# sensors.net
KiCad netlist of a schematic drawn in EAGLE
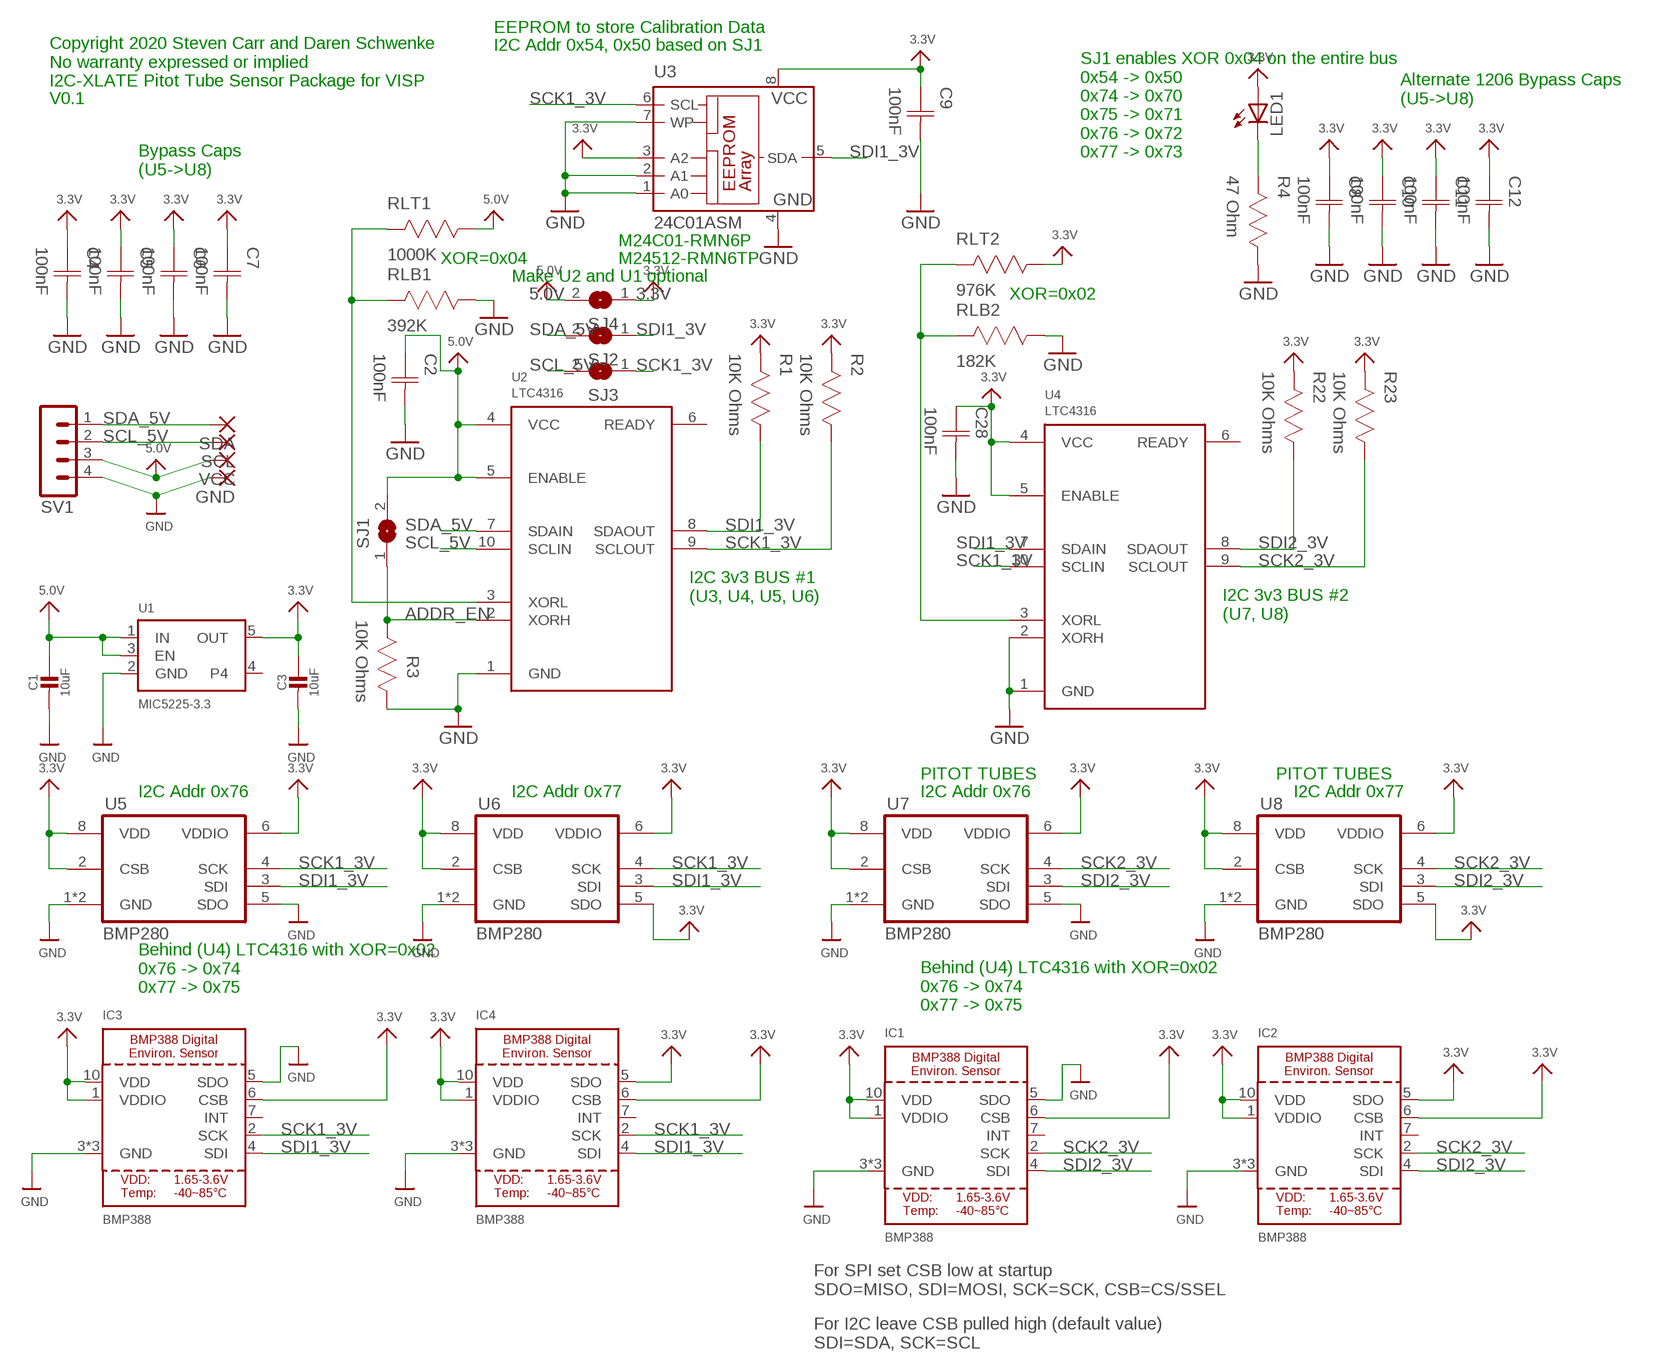
[diagram p0: schematic, sheet 1]

(export (version "E")
  (design (tool "Eeschema 10.0.6"))
  (components
    (comp (ref "C1")
      (value "10uF")
      (footprint "eagle-import:0603-NO")
      (fields (field (name "MPN") "C1608X5R1A106M080AC"))
      (libsource (lib "eagle-import") (part "CAP_CERAMIC0603_NO"))
    )
    (comp (ref "C2")
      (value "100nF")
      (footprint "eagle-import:CAP0603")
      (fields (field (name "MPN") "CL10B104KB8NNNC"))
      (libsource (lib "eagle-import") (part "CAPACITOR-0603"))
    )
    (comp (ref "C3")
      (value "10uF")
      (footprint "eagle-import:0603-NO")
      (fields (field (name "MPN") "C1608X5R1A106M080AC"))
      (libsource (lib "eagle-import") (part "CAP_CERAMIC0603_NO"))
    )
    (comp (ref "C4")
      (value "100nF")
      (footprint "eagle-import:CAP0402")
      (fields (field (name "MPN") " CL10F104ZO8NNNC "))
      (libsource (lib "eagle-import") (part "CAPACITOR-0402"))
    )
    (comp (ref "C5")
      (value "100nF")
      (footprint "eagle-import:CAP0402")
      (fields (field (name "MPN") " CL10F104ZO8NNNC "))
      (libsource (lib "eagle-import") (part "CAPACITOR-0402"))
    )
    (comp (ref "C6")
      (value "100nF")
      (footprint "eagle-import:CAP0402")
      (fields (field (name "MPN") " CL10F104ZO8NNNC "))
      (libsource (lib "eagle-import") (part "CAPACITOR-0402"))
    )
    (comp (ref "C7")
      (value "100nF")
      (footprint "eagle-import:CAP0402")
      (fields (field (name "MPN") " CL10F104ZO8NNNC "))
      (libsource (lib "eagle-import") (part "CAPACITOR-0402"))
    )
    (comp (ref "C8")
      (value "100nF")
      (footprint "eagle-import:CAP1206")
      (fields (field (name "MPN") "C1206C104K5RAC7800 "))
      (libsource (lib "eagle-import") (part "CAPACITOR-1206"))
    )
    (comp (ref "C9")
      (value "100nF")
      (footprint "eagle-import:CAP0603")
      (fields (field (name "MPN") "CL10B104KB8NNNC"))
      (libsource (lib "eagle-import") (part "CAPACITOR-0603"))
    )
    (comp (ref "C10")
      (value "100nF")
      (footprint "eagle-import:CAP1206")
      (fields (field (name "MPN") "C1206C104K5RAC7800 "))
      (libsource (lib "eagle-import") (part "CAPACITOR-1206"))
    )
    (comp (ref "C11")
      (value "100nF")
      (footprint "eagle-import:CAP1206")
      (fields (field (name "MPN") "C1206C104K5RAC7800 "))
      (libsource (lib "eagle-import") (part "CAPACITOR-1206"))
    )
    (comp (ref "C12")
      (value "100nF")
      (footprint "eagle-import:CAP1206")
      (fields (field (name "MPN") "C1206C104K5RAC7800 "))
      (libsource (lib "eagle-import") (part "CAPACITOR-1206"))
    )
    (comp (ref "C28")
      (value "100nF")
      (footprint "eagle-import:CAP0603")
      (fields (field (name "MPN") "CL10B104KB8NNNC"))
      (libsource (lib "eagle-import") (part "CAPACITOR-0603"))
    )
    (comp (ref "GND")
      (value "SMD2")
      (footprint "eagle-import:SMD1,27-2,54")
      (libsource (lib "eagle-import") (part "SMD2"))
    )
    (comp (ref "IC1")
      (value "BMP388")
      (footprint "eagle-import:BMP388")
      (libsource (lib "eagle-import") (part "BMP388"))
    )
    (comp (ref "IC2")
      (value "BMP388")
      (footprint "eagle-import:BMP388")
      (libsource (lib "eagle-import") (part "BMP388"))
    )
    (comp (ref "IC3")
      (value "BMP388")
      (footprint "eagle-import:BMP388")
      (libsource (lib "eagle-import") (part "BMP388"))
    )
    (comp (ref "IC4")
      (value "BMP388")
      (footprint "eagle-import:BMP388")
      (libsource (lib "eagle-import") (part "BMP388"))
    )
    (comp (ref "LED1")
      (value "LEDCHIP-LED0603")
      (footprint "eagle-import:CHIP-LED0603")
      (fields (field (name "MPN") "SML-D12P8WT86"))
      (libsource (lib "eagle-import") (part "LEDCHIP-LED0603"))
    )
    (comp (ref "R1")
      (value "10K Ohms")
      (footprint "eagle-import:RES0603")
      (fields (field (name "MPN") "CRCW060310K0FKEAC"))
      (libsource (lib "eagle-import") (part "RESISTOR-0603"))
    )
    (comp (ref "R2")
      (value "10K Ohms")
      (footprint "eagle-import:RES0603")
      (fields (field (name "MPN") "CRCW060310K0FKEAC"))
      (libsource (lib "eagle-import") (part "RESISTOR-0603"))
    )
    (comp (ref "R3")
      (value "10K Ohms")
      (footprint "eagle-import:RES0603")
      (fields (field (name "MPN") "CL10B104KB8NNNC"))
      (libsource (lib "eagle-import") (part "RESISTOR-0603"))
    )
    (comp (ref "R4")
      (value "47 Ohm")
      (footprint "eagle-import:RES0603")
      (fields (field (name "MPN") "RC0603FR-0747RL"))
      (libsource (lib "eagle-import") (part "RESISTOR-0603"))
    )
    (comp (ref "R22")
      (value "10K Ohms")
      (footprint "eagle-import:RES0603")
      (fields (field (name "MPN") "CRCW060310K0FKEAC"))
      (libsource (lib "eagle-import") (part "RESISTOR-0603"))
    )
    (comp (ref "R23")
      (value "10K Ohms")
      (footprint "eagle-import:RES0603")
      (fields (field (name "MPN") "CRCW060310K0FKEAC"))
      (libsource (lib "eagle-import") (part "RESISTOR-0603"))
    )
    (comp (ref "RLB1")
      (value "392K")
      (footprint "eagle-import:RES0603")
      (fields (field (name "MPN") " RC0603FR-07392KL "))
      (libsource (lib "eagle-import") (part "RESISTOR-0603"))
    )
    (comp (ref "RLB2")
      (value "182K")
      (footprint "eagle-import:RES0603")
      (fields (field (name "MPN") " RC0603FR-07182KL "))
      (libsource (lib "eagle-import") (part "RESISTOR-0603"))
    )
    (comp (ref "RLT1")
      (value "1000K")
      (footprint "eagle-import:RES0603")
      (fields (field (name "MPN") "CRCW060310K0FKEAC"))
      (libsource (lib "eagle-import") (part "RESISTOR-0603"))
    )
    (comp (ref "RLT2")
      (value "976K")
      (footprint "eagle-import:RES0603")
      (fields (field (name "MPN") "RC0603FR-07976KL"))
      (libsource (lib "eagle-import") (part "RESISTOR-0603"))
    )
    (comp (ref "SCL")
      (value "SMD2")
      (footprint "eagle-import:SMD1,27-2,54")
      (libsource (lib "eagle-import") (part "SMD2"))
    )
    (comp (ref "SDA")
      (value "SMD2")
      (footprint "eagle-import:SMD1,27-2,54")
      (libsource (lib "eagle-import") (part "SMD2"))
    )
    (comp (ref "SJ1") (value "SJ") (footprint "eagle-import:SJ") (libsource (lib "eagle-import") (part "SJ")))
    (comp (ref "SJ2") (value "SJ") (footprint "eagle-import:SJ") (libsource (lib "eagle-import") (part "SJ")))
    (comp (ref "SJ3") (value "SJ") (footprint "eagle-import:SJ") (libsource (lib "eagle-import") (part "SJ")))
    (comp (ref "SJ4") (value "SJ") (footprint "eagle-import:SJ") (libsource (lib "eagle-import") (part "SJ")))
    (comp (ref "SV1")
      (value "MA04-1")
      (footprint "eagle-import:MA04-1")
      (libsource (lib "eagle-import") (part "MA04-1"))
    )
    (comp (ref "U1")
      (value "MIC5225-3.3")
      (footprint "eagle-import:SOT23-5")
      (fields (field (name "MPN") "MIC5225-3.3YM5-TR"))
      (libsource (lib "eagle-import") (part "VREG_SOT23-5"))
    )
    (comp (ref "U2")
      (value "LTC4316")
      (footprint "eagle-import:MSOP10")
      (fields (field (name "MPN") "LTC4316IMS#PBF"))
      (libsource (lib "eagle-import") (part "LTC4316"))
    )
    (comp (ref "U3")
      (value "24C01ASM")
      (footprint "eagle-import:SO-08M")
      (fields
        (field (name "MF") "MICROCHIP")
        (field (name "MPN") "24C01C/SN")
        (field (name "MPN_1") "M24C01-RMN6P")
      )
      (libsource (lib "eagle-import") (part "24SMC01A"))
    )
    (comp (ref "U4")
      (value "LTC4316")
      (footprint "eagle-import:MSOP10")
      (fields (field (name "MPN") "LTC4316IMS#PBF"))
      (libsource (lib "eagle-import") (part "LTC4316"))
    )
    (comp (ref "U5")
      (value "BMP280")
      (footprint "eagle-import:BMP280")
      (libsource (lib "eagle-import") (part "BMP280"))
    )
    (comp (ref "U6")
      (value "BMP280")
      (footprint "eagle-import:BMP280")
      (libsource (lib "eagle-import") (part "BMP280"))
    )
    (comp (ref "U7")
      (value "BMP280")
      (footprint "eagle-import:BMP280")
      (libsource (lib "eagle-import") (part "BMP280"))
    )
    (comp (ref "U8")
      (value "BMP280")
      (footprint "eagle-import:BMP280")
      (libsource (lib "eagle-import") (part "BMP280"))
    )
    (comp (ref "VCC")
      (value "SMD2")
      (footprint "eagle-import:SMD1,27-2,54")
      (libsource (lib "eagle-import") (part "SMD2"))
    )
  )
  (nets
    (net (code "1") (name "/ADDR_EN") (class "Default")
      (node (ref "R3") (pin "2") (pinfunction "2_2") (pintype "passive"))
      (node (ref "SJ1") (pin "1") (pinfunction "1_1") (pintype "passive"))
      (node (ref "U2") (pin "2") (pinfunction "XORH_2") (pintype "bidirectional"))
    )
    (net (code "2") (name "/SCK1_3V") (class "Default")
      (node (ref "IC3") (pin "2") (pinfunction "SCK_2") (pintype "input"))
      (node (ref "IC4") (pin "2") (pinfunction "SCK_2") (pintype "input"))
      (node (ref "R2") (pin "1") (pinfunction "1_1") (pintype "passive"))
      (node (ref "SJ3") (pin "1") (pinfunction "1_1") (pintype "passive"))
      (node (ref "U2") (pin "9") (pinfunction "SCLOUT_9") (pintype "bidirectional"))
      (node (ref "U3") (pin "6") (pinfunction "SCL_6") (pintype "input"))
      (node (ref "U4") (pin "10") (pinfunction "SCLIN_10") (pintype "bidirectional"))
      (node (ref "U5") (pin "4") (pinfunction "SCK_4") (pintype "bidirectional"))
      (node (ref "U6") (pin "4") (pinfunction "SCK_4") (pintype "bidirectional"))
    )
    (net (code "3") (name "/SCK2_3V") (class "Default")
      (node (ref "IC1") (pin "2") (pinfunction "SCK_2") (pintype "input"))
      (node (ref "IC2") (pin "2") (pinfunction "SCK_2") (pintype "input"))
      (node (ref "R23") (pin "1") (pinfunction "1_1") (pintype "passive"))
      (node (ref "U4") (pin "9") (pinfunction "SCLOUT_9") (pintype "bidirectional"))
      (node (ref "U7") (pin "4") (pinfunction "SCK_4") (pintype "bidirectional"))
      (node (ref "U8") (pin "4") (pinfunction "SCK_4") (pintype "bidirectional"))
    )
    (net (code "4") (name "/SCL_5V") (class "Default")
      (node (ref "SCL") (pin "1") (pinfunction "P_1") (pintype "passive"))
      (node (ref "SJ3") (pin "2") (pinfunction "2_2") (pintype "passive"))
      (node (ref "SV1") (pin "2") (pinfunction "2_2") (pintype "passive"))
      (node (ref "U2") (pin "10") (pinfunction "SCLIN_10") (pintype "bidirectional"))
    )
    (net (code "5") (name "/SDA_5V") (class "Default")
      (node (ref "SDA") (pin "1") (pinfunction "P_1") (pintype "passive"))
      (node (ref "SJ2") (pin "2") (pinfunction "2_2") (pintype "passive"))
      (node (ref "SV1") (pin "1") (pinfunction "1_1") (pintype "passive"))
      (node (ref "U2") (pin "7") (pinfunction "SDAIN_7") (pintype "bidirectional"))
    )
    (net (code "6") (name "/SDI1_3V") (class "Default")
      (node (ref "IC3") (pin "4") (pinfunction "SDI_4") (pintype "input"))
      (node (ref "IC4") (pin "4") (pinfunction "SDI_4") (pintype "input"))
      (node (ref "R1") (pin "1") (pinfunction "1_1") (pintype "passive"))
      (node (ref "SJ2") (pin "1") (pinfunction "1_1") (pintype "passive"))
      (node (ref "U2") (pin "8") (pinfunction "SDAOUT_8") (pintype "bidirectional"))
      (node (ref "U3") (pin "5") (pinfunction "SDA_5") (pintype "bidirectional"))
      (node (ref "U4") (pin "7") (pinfunction "SDAIN_7") (pintype "bidirectional"))
      (node (ref "U5") (pin "3") (pinfunction "SDI_3") (pintype "bidirectional"))
      (node (ref "U6") (pin "3") (pinfunction "SDI_3") (pintype "bidirectional"))
    )
    (net (code "7") (name "/SDI2_3V") (class "Default")
      (node (ref "IC1") (pin "4") (pinfunction "SDI_4") (pintype "input"))
      (node (ref "IC2") (pin "4") (pinfunction "SDI_4") (pintype "input"))
      (node (ref "R22") (pin "1") (pinfunction "1_1") (pintype "passive"))
      (node (ref "U4") (pin "8") (pinfunction "SDAOUT_8") (pintype "bidirectional"))
      (node (ref "U7") (pin "3") (pinfunction "SDI_3") (pintype "bidirectional"))
      (node (ref "U8") (pin "3") (pinfunction "SDI_3") (pintype "bidirectional"))
    )
    (net (code "8") (name "3.3V") (class "Default")
      (node (ref "C10") (pin "1") (pinfunction "C1_1") (pintype "passive"))
      (node (ref "C11") (pin "1") (pinfunction "C1_1") (pintype "passive"))
      (node (ref "C12") (pin "1") (pinfunction "C1_1") (pintype "passive"))
      (node (ref "C28") (pin "1") (pinfunction "C1_1") (pintype "passive"))
      (node (ref "C3") (pin "1") (pinfunction "1_1") (pintype "passive"))
      (node (ref "C4") (pin "1") (pinfunction "C1_1") (pintype "passive"))
      (node (ref "C5") (pin "1") (pinfunction "C1_1") (pintype "passive"))
      (node (ref "C6") (pin "1") (pinfunction "C1_1") (pintype "passive"))
      (node (ref "C7") (pin "1") (pinfunction "C1_1") (pintype "passive"))
      (node (ref "C8") (pin "1") (pinfunction "C1_1") (pintype "passive"))
      (node (ref "C9") (pin "1") (pinfunction "C1_1") (pintype "passive"))
      (node (ref "IC1") (pin "1") (pinfunction "VDDIO_1") (pintype "power_in"))
      (node (ref "IC1") (pin "10") (pinfunction "VDD_10") (pintype "power_in"))
      (node (ref "IC1") (pin "6") (pinfunction "CSB_6") (pintype "input"))
      (node (ref "IC2") (pin "1") (pinfunction "VDDIO_1") (pintype "power_in"))
      (node (ref "IC2") (pin "10") (pinfunction "VDD_10") (pintype "power_in"))
      (node (ref "IC2") (pin "5") (pinfunction "SDO_5") (pintype "output"))
      (node (ref "IC2") (pin "6") (pinfunction "CSB_6") (pintype "input"))
      (node (ref "IC3") (pin "1") (pinfunction "VDDIO_1") (pintype "power_in"))
      (node (ref "IC3") (pin "10") (pinfunction "VDD_10") (pintype "power_in"))
      (node (ref "IC3") (pin "6") (pinfunction "CSB_6") (pintype "input"))
      (node (ref "IC4") (pin "1") (pinfunction "VDDIO_1") (pintype "power_in"))
      (node (ref "IC4") (pin "10") (pinfunction "VDD_10") (pintype "power_in"))
      (node (ref "IC4") (pin "5") (pinfunction "SDO_5") (pintype "output"))
      (node (ref "IC4") (pin "6") (pinfunction "CSB_6") (pintype "input"))
      (node (ref "LED1") (pin "A") (pinfunction "A_A") (pintype "passive"))
      (node (ref "R1") (pin "2") (pinfunction "2_2") (pintype "passive"))
      (node (ref "R2") (pin "2") (pinfunction "2_2") (pintype "passive"))
      (node (ref "R22") (pin "2") (pinfunction "2_2") (pintype "passive"))
      (node (ref "R23") (pin "2") (pinfunction "2_2") (pintype "passive"))
      (node (ref "RLT2") (pin "1") (pinfunction "1_1") (pintype "passive"))
      (node (ref "SJ4") (pin "1") (pinfunction "1_1") (pintype "passive"))
      (node (ref "U1") (pin "5") (pinfunction "OUT_5") (pintype "power_in"))
      (node (ref "U3") (pin "3") (pinfunction "A2_3") (pintype "input"))
      (node (ref "U3") (pin "8") (pinfunction "VCC_8") (pintype "power_in"))
      (node (ref "U4") (pin "4") (pinfunction "VCC_4") (pintype "bidirectional"))
      (node (ref "U4") (pin "5") (pinfunction "ENABLE_5") (pintype "bidirectional"))
      (node (ref "U5") (pin "2") (pinfunction "CSB_2") (pintype "input"))
      (node (ref "U5") (pin "6") (pinfunction "VDDIO_6") (pintype "power_in"))
      (node (ref "U5") (pin "8") (pinfunction "VDD_8") (pintype "power_in"))
      (node (ref "U6") (pin "2") (pinfunction "CSB_2") (pintype "input"))
      (node (ref "U6") (pin "5") (pinfunction "SDO_5") (pintype "input"))
      (node (ref "U6") (pin "6") (pinfunction "VDDIO_6") (pintype "power_in"))
      (node (ref "U6") (pin "8") (pinfunction "VDD_8") (pintype "power_in"))
      (node (ref "U7") (pin "2") (pinfunction "CSB_2") (pintype "input"))
      (node (ref "U7") (pin "6") (pinfunction "VDDIO_6") (pintype "power_in"))
      (node (ref "U7") (pin "8") (pinfunction "VDD_8") (pintype "power_in"))
      (node (ref "U8") (pin "2") (pinfunction "CSB_2") (pintype "input"))
      (node (ref "U8") (pin "5") (pinfunction "SDO_5") (pintype "input"))
      (node (ref "U8") (pin "6") (pinfunction "VDDIO_6") (pintype "power_in"))
      (node (ref "U8") (pin "8") (pinfunction "VDD_8") (pintype "power_in"))
    )
    (net (code "9") (name "5.0V") (class "Default")
      (node (ref "C1") (pin "1") (pinfunction "1_1") (pintype "passive"))
      (node (ref "C2") (pin "1") (pinfunction "C1_1") (pintype "passive"))
      (node (ref "RLT1") (pin "1") (pinfunction "1_1") (pintype "passive"))
      (node (ref "SJ1") (pin "2") (pinfunction "2_2") (pintype "passive"))
      (node (ref "SJ4") (pin "2") (pinfunction "2_2") (pintype "passive"))
      (node (ref "SV1") (pin "3") (pinfunction "3_3") (pintype "passive"))
      (node (ref "U1") (pin "1") (pinfunction "IN_1") (pintype "power_in"))
      (node (ref "U1") (pin "3") (pinfunction "EN_3") (pintype "input"))
      (node (ref "U2") (pin "4") (pinfunction "VCC_4") (pintype "bidirectional"))
      (node (ref "U2") (pin "5") (pinfunction "ENABLE_5") (pintype "bidirectional"))
      (node (ref "VCC") (pin "1") (pinfunction "P_1") (pintype "passive"))
    )
    (net (code "10") (name "GND") (class "Default")
      (node (ref "C1") (pin "2") (pinfunction "2_2") (pintype "passive"))
      (node (ref "C10") (pin "2") (pinfunction "C2_2") (pintype "passive"))
      (node (ref "C11") (pin "2") (pinfunction "C2_2") (pintype "passive"))
      (node (ref "C12") (pin "2") (pinfunction "C2_2") (pintype "passive"))
      (node (ref "C2") (pin "2") (pinfunction "C2_2") (pintype "passive"))
      (node (ref "C28") (pin "2") (pinfunction "C2_2") (pintype "passive"))
      (node (ref "C3") (pin "2") (pinfunction "2_2") (pintype "passive"))
      (node (ref "C4") (pin "2") (pinfunction "C2_2") (pintype "passive"))
      (node (ref "C5") (pin "2") (pinfunction "C2_2") (pintype "passive"))
      (node (ref "C6") (pin "2") (pinfunction "C2_2") (pintype "passive"))
      (node (ref "C7") (pin "2") (pinfunction "C2_2") (pintype "passive"))
      (node (ref "C8") (pin "2") (pinfunction "C2_2") (pintype "passive"))
      (node (ref "C9") (pin "2") (pinfunction "C2_2") (pintype "passive"))
      (node (ref "GND") (pin "1") (pinfunction "P_1") (pintype "passive"))
      (node (ref "IC1") (pin "3") (pinfunction "GND_3") (pintype "power_in"))
      (node (ref "IC1") (pin "5") (pinfunction "SDO_5") (pintype "output"))
      (node (ref "IC1") (pin "8") (pinfunction "GND_8") (pintype "power_in"))
      (node (ref "IC1") (pin "9") (pinfunction "GND_9") (pintype "power_in"))
      (node (ref "IC2") (pin "3") (pinfunction "GND_3") (pintype "power_in"))
      (node (ref "IC2") (pin "8") (pinfunction "GND_8") (pintype "power_in"))
      (node (ref "IC2") (pin "9") (pinfunction "GND_9") (pintype "power_in"))
      (node (ref "IC3") (pin "3") (pinfunction "GND_3") (pintype "power_in"))
      (node (ref "IC3") (pin "5") (pinfunction "SDO_5") (pintype "output"))
      (node (ref "IC3") (pin "8") (pinfunction "GND_8") (pintype "power_in"))
      (node (ref "IC3") (pin "9") (pinfunction "GND_9") (pintype "power_in"))
      (node (ref "IC4") (pin "3") (pinfunction "GND_3") (pintype "power_in"))
      (node (ref "IC4") (pin "8") (pinfunction "GND_8") (pintype "power_in"))
      (node (ref "IC4") (pin "9") (pinfunction "GND_9") (pintype "power_in"))
      (node (ref "R3") (pin "1") (pinfunction "1_1") (pintype "passive"))
      (node (ref "R4") (pin "1") (pinfunction "1_1") (pintype "passive"))
      (node (ref "RLB1") (pin "1") (pinfunction "1_1") (pintype "passive"))
      (node (ref "RLB2") (pin "1") (pinfunction "1_1") (pintype "passive"))
      (node (ref "SV1") (pin "4") (pinfunction "4_4") (pintype "passive"))
      (node (ref "U1") (pin "2") (pinfunction "GND_2") (pintype "power_in"))
      (node (ref "U2") (pin "1") (pinfunction "GND_1") (pintype "bidirectional"))
      (node (ref "U3") (pin "1") (pinfunction "A0_1") (pintype "input"))
      (node (ref "U3") (pin "2") (pinfunction "A1_2") (pintype "input"))
      (node (ref "U3") (pin "4") (pinfunction "GND_4") (pintype "power_in"))
      (node (ref "U3") (pin "7") (pinfunction "WP_7") (pintype "input"))
      (node (ref "U4") (pin "1") (pinfunction "GND_1") (pintype "bidirectional"))
      (node (ref "U4") (pin "2") (pinfunction "XORH_2") (pintype "bidirectional"))
      (node (ref "U5") (pin "1") (pinfunction "GND_1") (pintype "power_in"))
      (node (ref "U5") (pin "5") (pinfunction "SDO_5") (pintype "input"))
      (node (ref "U5") (pin "7") (pinfunction "GND_7") (pintype "power_in"))
      (node (ref "U6") (pin "1") (pinfunction "GND_1") (pintype "power_in"))
      (node (ref "U6") (pin "7") (pinfunction "GND_7") (pintype "power_in"))
      (node (ref "U7") (pin "1") (pinfunction "GND_1") (pintype "power_in"))
      (node (ref "U7") (pin "5") (pinfunction "SDO_5") (pintype "input"))
      (node (ref "U7") (pin "7") (pinfunction "GND_7") (pintype "power_in"))
      (node (ref "U8") (pin "1") (pinfunction "GND_1") (pintype "power_in"))
      (node (ref "U8") (pin "7") (pinfunction "GND_7") (pintype "power_in"))
    )
    (net (code "11") (name "Net-(LED1-PadC)") (class "Default")
      (node (ref "LED1") (pin "C") (pinfunction "C_C") (pintype "passive"))
      (node (ref "R4") (pin "2") (pinfunction "2_2") (pintype "passive"))
    )
    (net (code "12") (name "Net-(U2-XORL)") (class "Default")
      (node (ref "RLB1") (pin "2") (pinfunction "2_2") (pintype "passive"))
      (node (ref "RLT1") (pin "2") (pinfunction "2_2") (pintype "passive"))
      (node (ref "U2") (pin "3") (pinfunction "XORL_3") (pintype "bidirectional"))
    )
    (net (code "13") (name "Net-(U4-XORL)") (class "Default")
      (node (ref "RLB2") (pin "2") (pinfunction "2_2") (pintype "passive"))
      (node (ref "RLT2") (pin "2") (pinfunction "2_2") (pintype "passive"))
      (node (ref "U4") (pin "3") (pinfunction "XORL_3") (pintype "bidirectional"))
    )
    (net (code "14") (name "unconnected-(IC1-INT-Pad7)") (class "Default")
      (node (ref "IC1") (pin "7") (pinfunction "INT_7") (pintype "output"))
    )
    (net (code "15") (name "unconnected-(IC2-INT-Pad7)") (class "Default")
      (node (ref "IC2") (pin "7") (pinfunction "INT_7") (pintype "output"))
    )
    (net (code "16") (name "unconnected-(IC3-INT-Pad7)") (class "Default")
      (node (ref "IC3") (pin "7") (pinfunction "INT_7") (pintype "output"))
    )
    (net (code "17") (name "unconnected-(IC4-INT-Pad7)") (class "Default")
      (node (ref "IC4") (pin "7") (pinfunction "INT_7") (pintype "output"))
    )
    (net (code "18") (name "unconnected-(U1-P4-Pad4)") (class "Default")
      (node (ref "U1") (pin "4") (pinfunction "P4_4") (pintype "bidirectional"))
    )
    (net (code "19") (name "unconnected-(U2-READY-Pad6)") (class "Default")
      (node (ref "U2") (pin "6") (pinfunction "READY_6") (pintype "bidirectional"))
    )
    (net (code "20") (name "unconnected-(U4-READY-Pad6)") (class "Default")
      (node (ref "U4") (pin "6") (pinfunction "READY_6") (pintype "bidirectional"))
    )
  )
)
